# navscreen_r0.net
KiCad netlist of a schematic drawn in EAGLE
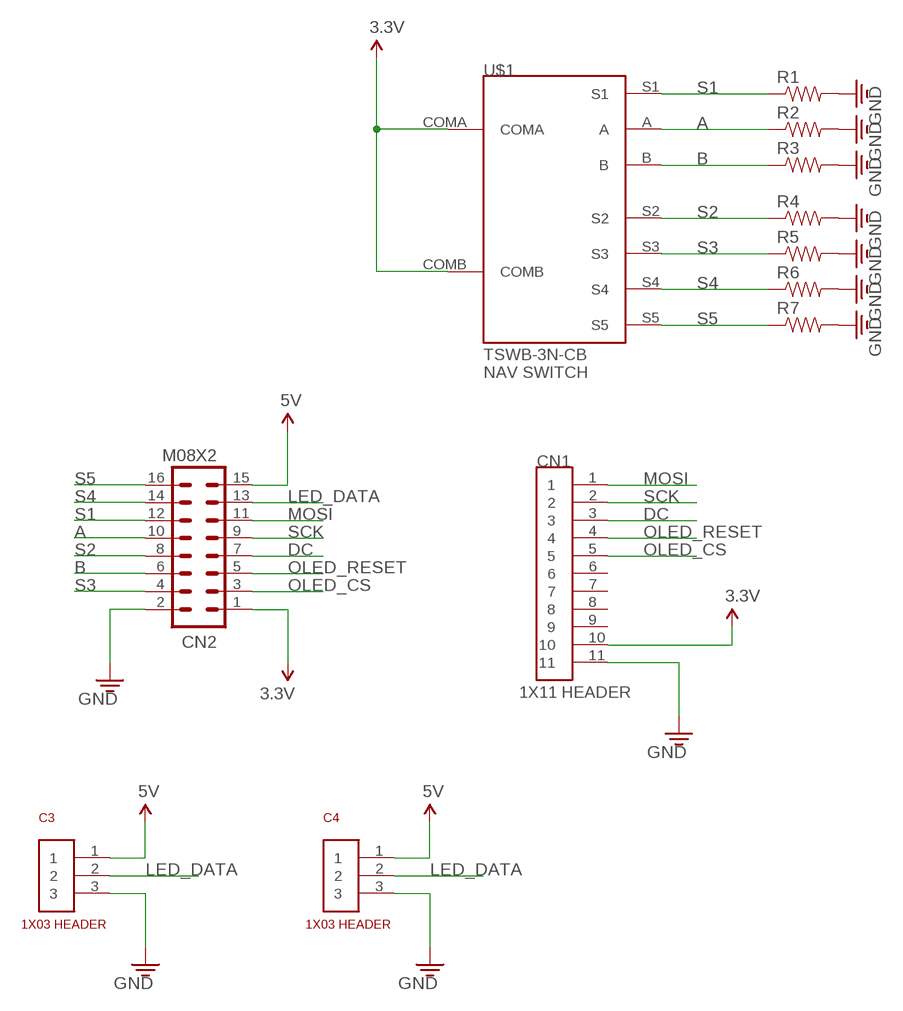
[diagram p0: schematic, sheet 1]

(export (version "E")
  (design (tool "Eeschema 10.0.6"))
  (components
    (comp (ref "C3")
      (value "1X03")
      (footprint "eagle-import:1X03")
      (libsource (lib "eagle-import") (part "1X03"))
    )
    (comp (ref "C4")
      (value "1X03")
      (footprint "eagle-import:1X03")
      (libsource (lib "eagle-import") (part "1X03"))
    )
    (comp (ref "CN1")
      (value "1X11")
      (footprint "eagle-import:1X11")
      (libsource (lib "eagle-import") (part "1X11"))
    )
    (comp (ref "CN2")
      (value "M08X2")
      (footprint "eagle-import:2X8")
      (libsource (lib "eagle-import") (part "M08X2"))
    )
    (comp (ref "R1")
      (value "RESISTOR0603")
      (footprint "eagle-import:0603")
      (libsource (lib "eagle-import") (part "RESISTOR0603"))
    )
    (comp (ref "R2")
      (value "RESISTOR0603")
      (footprint "eagle-import:0603")
      (libsource (lib "eagle-import") (part "RESISTOR0603"))
    )
    (comp (ref "R3")
      (value "RESISTOR0603")
      (footprint "eagle-import:0603")
      (libsource (lib "eagle-import") (part "RESISTOR0603"))
    )
    (comp (ref "R4")
      (value "RESISTOR0603")
      (footprint "eagle-import:0603")
      (libsource (lib "eagle-import") (part "RESISTOR0603"))
    )
    (comp (ref "R5")
      (value "RESISTOR0603")
      (footprint "eagle-import:0603")
      (libsource (lib "eagle-import") (part "RESISTOR0603"))
    )
    (comp (ref "R6")
      (value "RESISTOR0603")
      (footprint "eagle-import:0603")
      (libsource (lib "eagle-import") (part "RESISTOR0603"))
    )
    (comp (ref "R7")
      (value "RESISTOR0603")
      (footprint "eagle-import:0603")
      (libsource (lib "eagle-import") (part "RESISTOR0603"))
    )
    (comp (ref "U$1")
      (value "NAV-SWITCH-TSWB-3N-CB")
      (footprint "eagle-import:TSWB-3N-CB")
      (libsource (lib "eagle-import") (part "NAV-SWITCH-TSWB-3N-CB"))
    )
  )
  (nets
    (net (code "1") (name "/A") (class "Default")
      (node (ref "CN2") (pin "10") (pinfunction "10_10") (pintype "passive"))
      (node (ref "R2") (pin "1") (pinfunction "1_1") (pintype "passive"))
      (node (ref "U$1") (pin "A") (pinfunction "A_A") (pintype "bidirectional"))
    )
    (net (code "2") (name "/B") (class "Default")
      (node (ref "CN2") (pin "6") (pinfunction "6_6") (pintype "passive"))
      (node (ref "R3") (pin "1") (pinfunction "1_1") (pintype "passive"))
      (node (ref "U$1") (pin "B") (pinfunction "B_B") (pintype "bidirectional"))
    )
    (net (code "3") (name "/DC") (class "Default")
      (node (ref "CN1") (pin "3") (pinfunction "3_3") (pintype "bidirectional"))
      (node (ref "CN2") (pin "7") (pinfunction "7_7") (pintype "passive"))
    )
    (net (code "4") (name "/LED_DATA") (class "Default")
      (node (ref "C3") (pin "2") (pinfunction "2_2") (pintype "bidirectional"))
      (node (ref "C4") (pin "2") (pinfunction "2_2") (pintype "bidirectional"))
      (node (ref "CN2") (pin "13") (pinfunction "13_13") (pintype "passive"))
    )
    (net (code "5") (name "/MOSI") (class "Default")
      (node (ref "CN1") (pin "1") (pinfunction "1_1") (pintype "bidirectional"))
      (node (ref "CN2") (pin "11") (pinfunction "11_11") (pintype "passive"))
    )
    (net (code "6") (name "/OLED_CS") (class "Default")
      (node (ref "CN1") (pin "5") (pinfunction "5_5") (pintype "bidirectional"))
      (node (ref "CN2") (pin "3") (pinfunction "3_3") (pintype "passive"))
    )
    (net (code "7") (name "/OLED_RESET") (class "Default")
      (node (ref "CN1") (pin "4") (pinfunction "4_4") (pintype "bidirectional"))
      (node (ref "CN2") (pin "5") (pinfunction "5_5") (pintype "passive"))
    )
    (net (code "8") (name "/S1") (class "Default")
      (node (ref "CN2") (pin "12") (pinfunction "12_12") (pintype "passive"))
      (node (ref "R1") (pin "1") (pinfunction "1_1") (pintype "passive"))
      (node (ref "U$1") (pin "S1") (pinfunction "S1_S1") (pintype "bidirectional"))
    )
    (net (code "9") (name "/S2") (class "Default")
      (node (ref "CN2") (pin "8") (pinfunction "8_8") (pintype "passive"))
      (node (ref "R4") (pin "1") (pinfunction "1_1") (pintype "passive"))
      (node (ref "U$1") (pin "S2") (pinfunction "S2_S2") (pintype "bidirectional"))
    )
    (net (code "10") (name "/S3") (class "Default")
      (node (ref "CN2") (pin "4") (pinfunction "4_4") (pintype "passive"))
      (node (ref "R5") (pin "1") (pinfunction "1_1") (pintype "passive"))
      (node (ref "U$1") (pin "S3") (pinfunction "S3_S3") (pintype "bidirectional"))
    )
    (net (code "11") (name "/S4") (class "Default")
      (node (ref "CN2") (pin "14") (pinfunction "14_14") (pintype "passive"))
      (node (ref "R6") (pin "1") (pinfunction "1_1") (pintype "passive"))
      (node (ref "U$1") (pin "S4") (pinfunction "S4_S4") (pintype "bidirectional"))
    )
    (net (code "12") (name "/S5") (class "Default")
      (node (ref "CN2") (pin "16") (pinfunction "16_16") (pintype "passive"))
      (node (ref "R7") (pin "1") (pinfunction "1_1") (pintype "passive"))
      (node (ref "U$1") (pin "S5") (pinfunction "S5_S5") (pintype "bidirectional"))
    )
    (net (code "13") (name "/SCK") (class "Default")
      (node (ref "CN1") (pin "2") (pinfunction "2_2") (pintype "bidirectional"))
      (node (ref "CN2") (pin "9") (pinfunction "9_9") (pintype "passive"))
    )
    (net (code "14") (name "3.3V") (class "Default")
      (node (ref "CN1") (pin "10") (pinfunction "10_10") (pintype "bidirectional"))
      (node (ref "CN2") (pin "1") (pinfunction "1_1") (pintype "passive"))
      (node (ref "U$1") (pin "COMA") (pinfunction "COMA_COMA") (pintype "bidirectional"))
      (node (ref "U$1") (pin "COMB") (pinfunction "COMB_COMB") (pintype "bidirectional"))
    )
    (net (code "15") (name "5V") (class "Default")
      (node (ref "C3") (pin "1") (pinfunction "1_1") (pintype "bidirectional"))
      (node (ref "C4") (pin "1") (pinfunction "1_1") (pintype "bidirectional"))
      (node (ref "CN2") (pin "15") (pinfunction "15_15") (pintype "passive"))
    )
    (net (code "16") (name "GND") (class "Default")
      (node (ref "C3") (pin "3") (pinfunction "3_3") (pintype "bidirectional"))
      (node (ref "C4") (pin "3") (pinfunction "3_3") (pintype "bidirectional"))
      (node (ref "CN1") (pin "11") (pinfunction "11_11") (pintype "bidirectional"))
      (node (ref "CN2") (pin "2") (pinfunction "2_2") (pintype "passive"))
      (node (ref "R1") (pin "2") (pinfunction "2_2") (pintype "passive"))
      (node (ref "R2") (pin "2") (pinfunction "2_2") (pintype "passive"))
      (node (ref "R3") (pin "2") (pinfunction "2_2") (pintype "passive"))
      (node (ref "R4") (pin "2") (pinfunction "2_2") (pintype "passive"))
      (node (ref "R5") (pin "2") (pinfunction "2_2") (pintype "passive"))
      (node (ref "R6") (pin "2") (pinfunction "2_2") (pintype "passive"))
      (node (ref "R7") (pin "2") (pinfunction "2_2") (pintype "passive"))
    )
    (net (code "17") (name "unconnected-(CN1-Pad6)") (class "Default")
      (node (ref "CN1") (pin "6") (pinfunction "6_6") (pintype "bidirectional"))
    )
    (net (code "18") (name "unconnected-(CN1-Pad7)") (class "Default")
      (node (ref "CN1") (pin "7") (pinfunction "7_7") (pintype "bidirectional"))
    )
    (net (code "19") (name "unconnected-(CN1-Pad8)") (class "Default")
      (node (ref "CN1") (pin "8") (pinfunction "8_8") (pintype "bidirectional"))
    )
    (net (code "20") (name "unconnected-(CN1-Pad9)") (class "Default")
      (node (ref "CN1") (pin "9") (pinfunction "9_9") (pintype "bidirectional"))
    )
  )
)
